# hot_spring.net
KiCad netlist of a schematic drawn in EAGLE
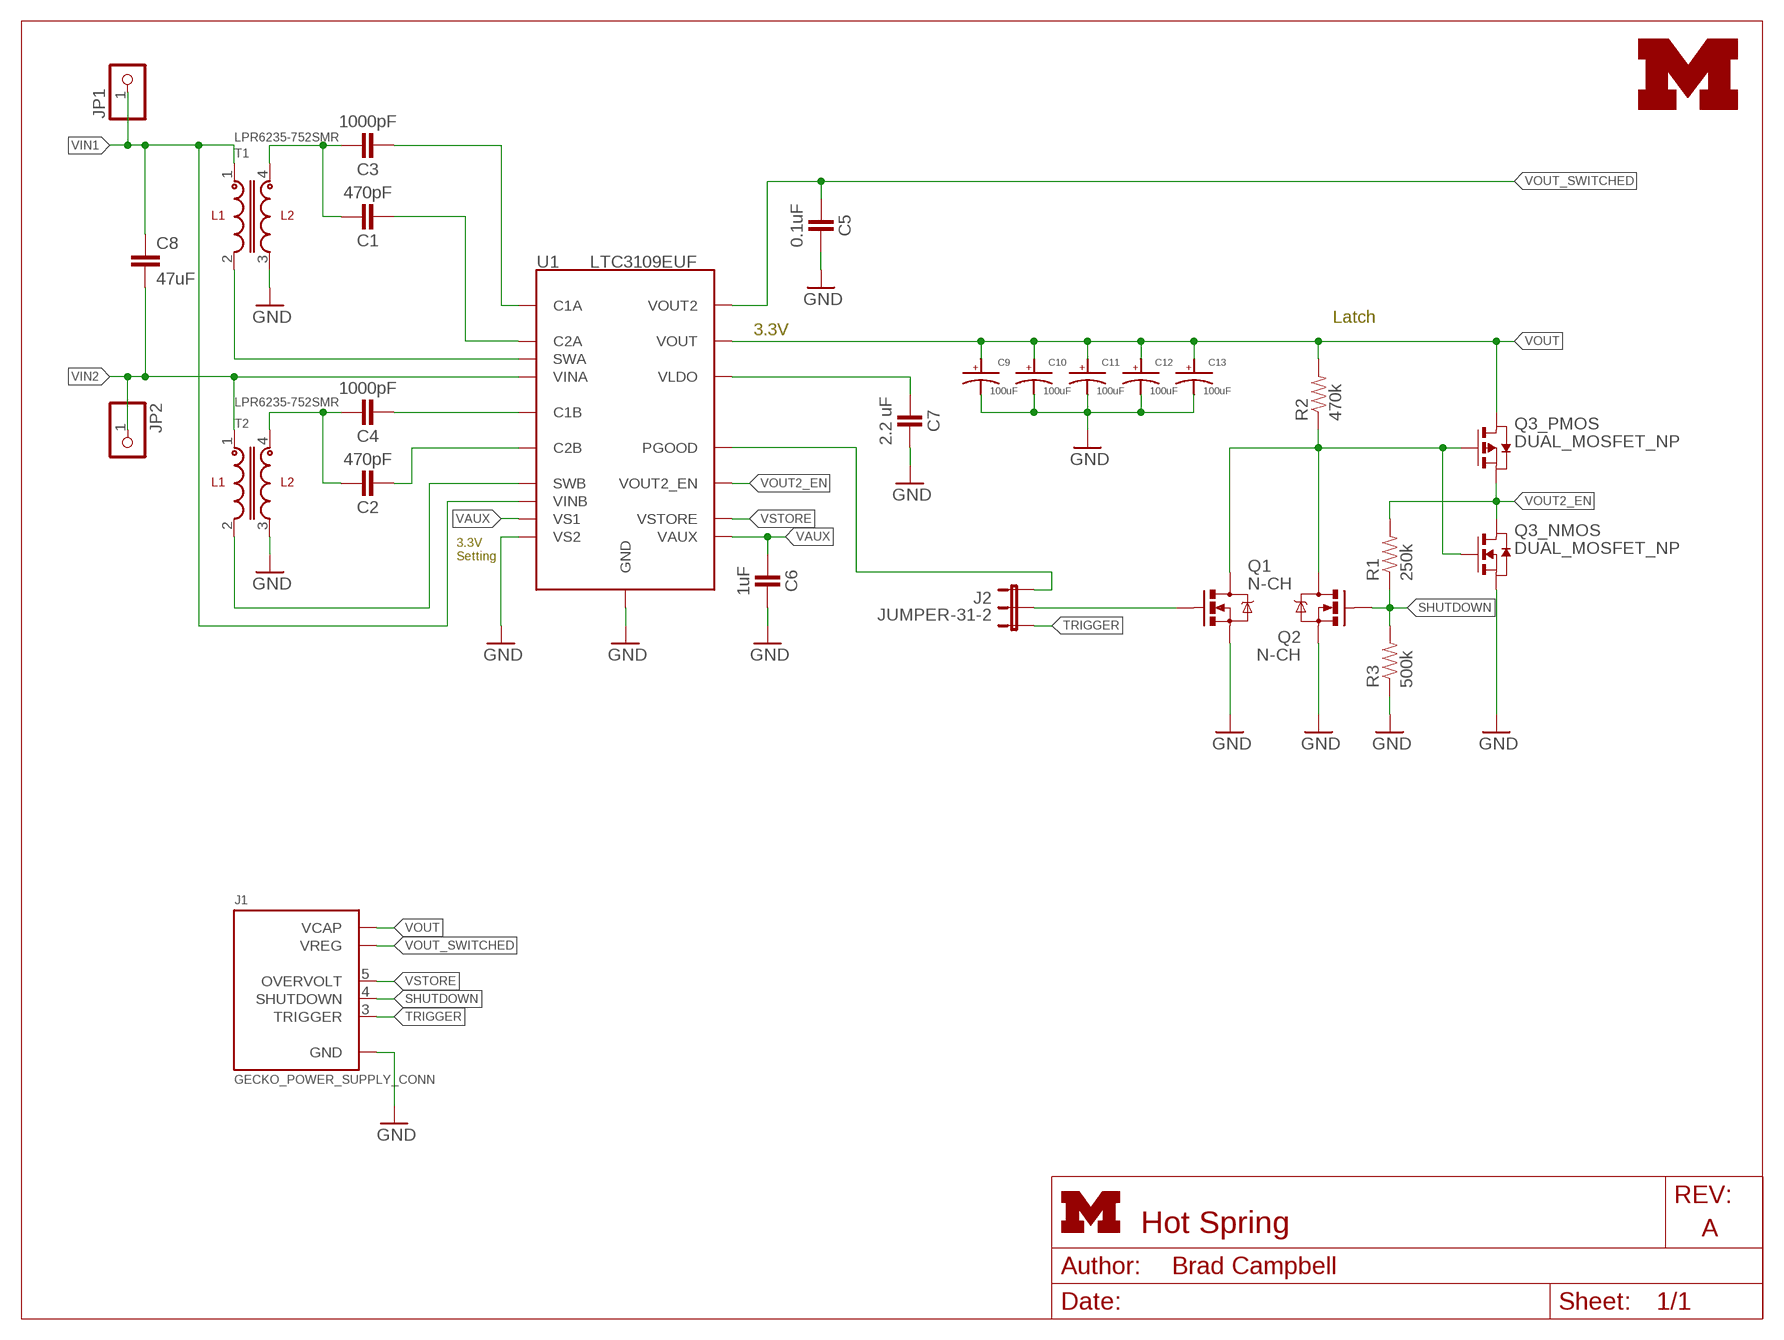
[diagram p0: schematic, sheet 1]

(export (version "E")
  (design (tool "Eeschema 10.0.6"))
  (components
    (comp (ref "C1")
      (value "470pF")
      (footprint "eagle-import:0402_CAP")
      (libsource (lib "eagle-import") (part "CAPACITOR"))
    )
    (comp (ref "C2")
      (value "470pF")
      (footprint "eagle-import:0402_CAP")
      (libsource (lib "eagle-import") (part "CAPACITOR"))
    )
    (comp (ref "C3")
      (value "1000pF")
      (footprint "eagle-import:0402_CAP")
      (libsource (lib "eagle-import") (part "CAPACITOR"))
    )
    (comp (ref "C4")
      (value "1000pF")
      (footprint "eagle-import:0402_CAP")
      (libsource (lib "eagle-import") (part "CAPACITOR"))
    )
    (comp (ref "C5")
      (value "0.1uF")
      (footprint "eagle-import:0402_CAP")
      (libsource (lib "eagle-import") (part "CAPACITOR"))
    )
    (comp (ref "C6")
      (value "1uF")
      (footprint "eagle-import:0402_CAP")
      (libsource (lib "eagle-import") (part "CAPACITOR"))
    )
    (comp (ref "C7")
      (value "2.2 uF")
      (footprint "eagle-import:0402_CAP")
      (libsource (lib "eagle-import") (part "CAPACITOR"))
    )
    (comp (ref "C8")
      (value "47uF")
      (footprint "eagle-import:1210")
      (libsource (lib "eagle-import") (part "CAP1210"))
    )
    (comp (ref "C9")
      (value "100uF")
      (footprint "eagle-import:CAP1210")
      (libsource (lib "eagle-import") (part "1210_CAP_POLARIZED"))
    )
    (comp (ref "C10")
      (value "100uF")
      (footprint "eagle-import:CAP1210")
      (libsource (lib "eagle-import") (part "1210_CAP_POLARIZED"))
    )
    (comp (ref "C11")
      (value "100uF")
      (footprint "eagle-import:CAP1210")
      (libsource (lib "eagle-import") (part "1210_CAP_POLARIZED"))
    )
    (comp (ref "C12")
      (value "100uF")
      (footprint "eagle-import:CAP1210")
      (libsource (lib "eagle-import") (part "1210_CAP_POLARIZED"))
    )
    (comp (ref "C13")
      (value "100uF")
      (footprint "eagle-import:CAP1210")
      (libsource (lib "eagle-import") (part "1210_CAP_POLARIZED"))
    )
    (comp (ref "J1")
      (value "GECKO_POWER_SUPPLY_CONN")
      (footprint "eagle-import:HEADER1X6_0.05IN")
      (libsource (lib "eagle-import") (part "GECKO_POWER_SUPPLY_CONN"))
    )
    (comp (ref "J2")
      (value "JUMPER-31-2")
      (footprint "eagle-import:SJ_3_PASTE1&2")
      (libsource (lib "eagle-import") (part "JUMPER-31-2"))
    )
    (comp (ref "JP1")
      (value "PINHD-1X1")
      (footprint "eagle-import:1X01")
      (libsource (lib "eagle-import") (part "PINHD-1X1"))
    )
    (comp (ref "JP2")
      (value "PINHD-1X1")
      (footprint "eagle-import:1X01")
      (libsource (lib "eagle-import") (part "PINHD-1X1"))
    )
    (comp (ref "LOGO1")
      (value "UMICH_SOLID_SMALL")
      (footprint "eagle-import:UMICH_SOLID_75MIL")
      (libsource (lib "eagle-import") (part "UMICH_SOLID_SMALL"))
    )
    (comp (ref "Q1")
      (value "MOSFET-NCHANNELSMD")
      (footprint "eagle-import:SOT23-3")
      (libsource (lib "eagle-import") (part "MOSFET-NCHANNELSMD"))
    )
    (comp (ref "Q2")
      (value "MOSFET-NCHANNELSMD")
      (footprint "eagle-import:SOT23-3")
      (libsource (lib "eagle-import") (part "MOSFET-NCHANNELSMD"))
    )
    (comp (ref "Q3")
      (value "DUAL_MOSFET_NP")
      (footprint "eagle-import:TSOP-6")
      (libsource (lib "eagle-import") (part "DUAL_MOSFET_NP"))
    )
    (comp (ref "R1")
      (value "250k")
      (footprint "eagle-import:0402_RES")
      (libsource (lib "eagle-import") (part "RESISTOR0402_RES"))
    )
    (comp (ref "R2")
      (value "470k")
      (footprint "eagle-import:0402_RES")
      (libsource (lib "eagle-import") (part "RESISTOR0402_RES"))
    )
    (comp (ref "R3")
      (value "500k")
      (footprint "eagle-import:0402_RES")
      (libsource (lib "eagle-import") (part "RESISTOR0402_RES"))
    )
    (comp (ref "T1")
      (value "LPR6235-752SMR")
      (footprint "eagle-import:LPR6235")
      (libsource (lib "eagle-import") (part "LPR6235-752SMR"))
    )
    (comp (ref "T2")
      (value "LPR6235-752SMR")
      (footprint "eagle-import:LPR6235")
      (libsource (lib "eagle-import") (part "LPR6235-752SMR"))
    )
    (comp (ref "U1")
      (value "LTC3109EUF")
      (footprint "eagle-import:QFN-20-4MM")
      (libsource (lib "eagle-import") (part "LTC3109EUF"))
    )
  )
  (nets
    (net (code "1") (name "GND") (class "Default")
      (node (ref "C10") (pin "ANODE") (pinfunction "ANODE_ANODE") (pintype "bidirectional"))
      (node (ref "C11") (pin "ANODE") (pinfunction "ANODE_ANODE") (pintype "bidirectional"))
      (node (ref "C12") (pin "ANODE") (pinfunction "ANODE_ANODE") (pintype "bidirectional"))
      (node (ref "C13") (pin "ANODE") (pinfunction "ANODE_ANODE") (pintype "bidirectional"))
      (node (ref "C5") (pin "1") (pinfunction "1_1") (pintype "bidirectional"))
      (node (ref "C6") (pin "1") (pinfunction "1_1") (pintype "bidirectional"))
      (node (ref "C7") (pin "1") (pinfunction "1_1") (pintype "bidirectional"))
      (node (ref "C9") (pin "ANODE") (pinfunction "ANODE_ANODE") (pintype "bidirectional"))
      (node (ref "J1") (pin "1") (pinfunction "GND_1") (pintype "bidirectional"))
      (node (ref "Q1") (pin "2") (pinfunction "S_2") (pintype "passive"))
      (node (ref "Q2") (pin "2") (pinfunction "S_2") (pintype "passive"))
      (node (ref "Q3") (pin "5") (pinfunction "S_5") (pintype "passive"))
      (node (ref "R3") (pin "1") (pinfunction "1_1") (pintype "passive"))
      (node (ref "T1") (pin "3") (pinfunction "3_3") (pintype "bidirectional"))
      (node (ref "T2") (pin "3") (pinfunction "3_3") (pintype "bidirectional"))
      (node (ref "U1") (pin "11") (pinfunction "GND_11") (pintype "bidirectional"))
      (node (ref "U1") (pin "16") (pinfunction "GND_16") (pintype "bidirectional"))
      (node (ref "U1") (pin "20") (pinfunction "VS2_20") (pintype "bidirectional"))
      (node (ref "U1") (pin "8") (pinfunction "GND_8") (pintype "bidirectional"))
      (node (ref "U1") (pin "GND") (pinfunction "GND_GND") (pintype "bidirectional"))
    )
    (net (code "2") (name "Net-(C1-Pad1)") (class "Default")
      (node (ref "C1") (pin "1") (pinfunction "1_1") (pintype "bidirectional"))
      (node (ref "C3") (pin "1") (pinfunction "1_1") (pintype "bidirectional"))
      (node (ref "T1") (pin "4") (pinfunction "4_4") (pintype "bidirectional"))
    )
    (net (code "3") (name "Net-(C2-Pad1)") (class "Default")
      (node (ref "C2") (pin "1") (pinfunction "1_1") (pintype "bidirectional"))
      (node (ref "C4") (pin "1") (pinfunction "1_1") (pintype "bidirectional"))
      (node (ref "T2") (pin "4") (pinfunction "4_4") (pintype "bidirectional"))
    )
    (net (code "4") (name "Net-(Q1-D)") (class "Default")
      (node (ref "Q1") (pin "3") (pinfunction "D_3") (pintype "passive"))
      (node (ref "Q2") (pin "3") (pinfunction "D_3") (pintype "passive"))
      (node (ref "Q3") (pin "1") (pinfunction "G_1") (pintype "passive"))
      (node (ref "Q3") (pin "3") (pinfunction "G_3") (pintype "passive"))
      (node (ref "R2") (pin "1") (pinfunction "1_1") (pintype "passive"))
    )
    (net (code "5") (name "Net-(Q1-G)") (class "Default")
      (node (ref "J2") (pin "2") (pinfunction "2_2") (pintype "passive"))
      (node (ref "Q1") (pin "1") (pinfunction "G_1") (pintype "passive"))
    )
    (net (code "6") (name "Net-(U1-C1A)") (class "Default")
      (node (ref "C3") (pin "2") (pinfunction "2_2") (pintype "bidirectional"))
      (node (ref "U1") (pin "18") (pinfunction "C1A_18") (pintype "bidirectional"))
    )
    (net (code "7") (name "Net-(U1-C1B)") (class "Default")
      (node (ref "C4") (pin "2") (pinfunction "2_2") (pintype "bidirectional"))
      (node (ref "U1") (pin "9") (pinfunction "C1B_9") (pintype "bidirectional"))
    )
    (net (code "8") (name "Net-(U1-C2A)") (class "Default")
      (node (ref "C1") (pin "2") (pinfunction "2_2") (pintype "bidirectional"))
      (node (ref "U1") (pin "17") (pinfunction "C2A_17") (pintype "bidirectional"))
    )
    (net (code "9") (name "Net-(U1-C2B)") (class "Default")
      (node (ref "C2") (pin "2") (pinfunction "2_2") (pintype "bidirectional"))
      (node (ref "U1") (pin "10") (pinfunction "C2B_10") (pintype "bidirectional"))
    )
    (net (code "10") (name "Net-(U1-PGOOD)") (class "Default")
      (node (ref "J2") (pin "1") (pinfunction "1_1") (pintype "passive"))
      (node (ref "U1") (pin "6") (pinfunction "PGOOD_6") (pintype "bidirectional"))
    )
    (net (code "11") (name "Net-(U1-SWA)") (class "Default")
      (node (ref "T1") (pin "2") (pinfunction "2_2") (pintype "bidirectional"))
      (node (ref "U1") (pin "15") (pinfunction "SWA_15") (pintype "bidirectional"))
    )
    (net (code "12") (name "Net-(U1-SWB)") (class "Default")
      (node (ref "T2") (pin "2") (pinfunction "2_2") (pintype "bidirectional"))
      (node (ref "U1") (pin "12") (pinfunction "SWB_12") (pintype "bidirectional"))
    )
    (net (code "13") (name "Net-(U1-VLDO)") (class "Default")
      (node (ref "C7") (pin "2") (pinfunction "2_2") (pintype "bidirectional"))
      (node (ref "U1") (pin "7") (pinfunction "VLDO_7") (pintype "bidirectional"))
    )
    (net (code "14") (name "SHUTDOWN") (class "Default")
      (node (ref "J1") (pin "4") (pinfunction "SHUTDOWN_4") (pintype "bidirectional"))
      (node (ref "Q2") (pin "1") (pinfunction "G_1") (pintype "passive"))
      (node (ref "R1") (pin "1") (pinfunction "1_1") (pintype "passive"))
      (node (ref "R3") (pin "2") (pinfunction "2_2") (pintype "passive"))
    )
    (net (code "15") (name "TRIGGER") (class "Default")
      (node (ref "J1") (pin "3") (pinfunction "TRIGGER_3") (pintype "bidirectional"))
      (node (ref "J2") (pin "3") (pinfunction "3_3") (pintype "passive"))
    )
    (net (code "16") (name "VAUX") (class "Default")
      (node (ref "C6") (pin "2") (pinfunction "2_2") (pintype "bidirectional"))
      (node (ref "U1") (pin "19") (pinfunction "VS1_19") (pintype "bidirectional"))
      (node (ref "U1") (pin "2") (pinfunction "VAUX_2") (pintype "bidirectional"))
    )
    (net (code "17") (name "VIN1") (class "Default")
      (node (ref "C8") (pin "1") (pinfunction "1_1") (pintype "passive"))
      (node (ref "JP1") (pin "1") (pinfunction "1_1") (pintype "passive"))
      (node (ref "T1") (pin "1") (pinfunction "1_1") (pintype "bidirectional"))
      (node (ref "U1") (pin "13") (pinfunction "VINB_13") (pintype "bidirectional"))
    )
    (net (code "18") (name "VIN2") (class "Default")
      (node (ref "C8") (pin "2") (pinfunction "2_2") (pintype "passive"))
      (node (ref "JP2") (pin "1") (pinfunction "1_1") (pintype "passive"))
      (node (ref "T2") (pin "1") (pinfunction "1_1") (pintype "bidirectional"))
      (node (ref "U1") (pin "14") (pinfunction "VINA_14") (pintype "bidirectional"))
    )
    (net (code "19") (name "VOUT") (class "Default")
      (node (ref "C10") (pin "CATHODE") (pinfunction "CATHODE_CATHODE") (pintype "bidirectional"))
      (node (ref "C11") (pin "CATHODE") (pinfunction "CATHODE_CATHODE") (pintype "bidirectional"))
      (node (ref "C12") (pin "CATHODE") (pinfunction "CATHODE_CATHODE") (pintype "bidirectional"))
      (node (ref "C13") (pin "CATHODE") (pinfunction "CATHODE_CATHODE") (pintype "bidirectional"))
      (node (ref "C9") (pin "CATHODE") (pinfunction "CATHODE_CATHODE") (pintype "bidirectional"))
      (node (ref "J1") (pin "6") (pinfunction "VCAP_6") (pintype "output"))
      (node (ref "Q3") (pin "4") (pinfunction "D_4") (pintype "passive"))
      (node (ref "R2") (pin "2") (pinfunction "2_2") (pintype "passive"))
      (node (ref "U1") (pin "3") (pinfunction "VOUT_3") (pintype "bidirectional"))
    )
    (net (code "20") (name "VOUT2_EN") (class "Default")
      (node (ref "Q3") (pin "2") (pinfunction "S_2") (pintype "passive"))
      (node (ref "Q3") (pin "6") (pinfunction "D_6") (pintype "passive"))
      (node (ref "R1") (pin "2") (pinfunction "2_2") (pintype "passive"))
      (node (ref "U1") (pin "5") (pinfunction "VOUT2_EN_5") (pintype "bidirectional"))
    )
    (net (code "21") (name "VOUT_SWITCHED") (class "Default")
      (node (ref "C5") (pin "2") (pinfunction "2_2") (pintype "bidirectional"))
      (node (ref "J1") (pin "2") (pinfunction "VREG_2") (pintype "bidirectional"))
      (node (ref "U1") (pin "4") (pinfunction "VOUT2_4") (pintype "bidirectional"))
    )
    (net (code "22") (name "VSTORE") (class "Default")
      (node (ref "J1") (pin "5") (pinfunction "OVERVOLT_5") (pintype "bidirectional"))
      (node (ref "U1") (pin "1") (pinfunction "VSTORE_1") (pintype "bidirectional"))
    )
  )
)
